# Sheet2.net
KiCad netlist of a schematic drawn in Altium Designer
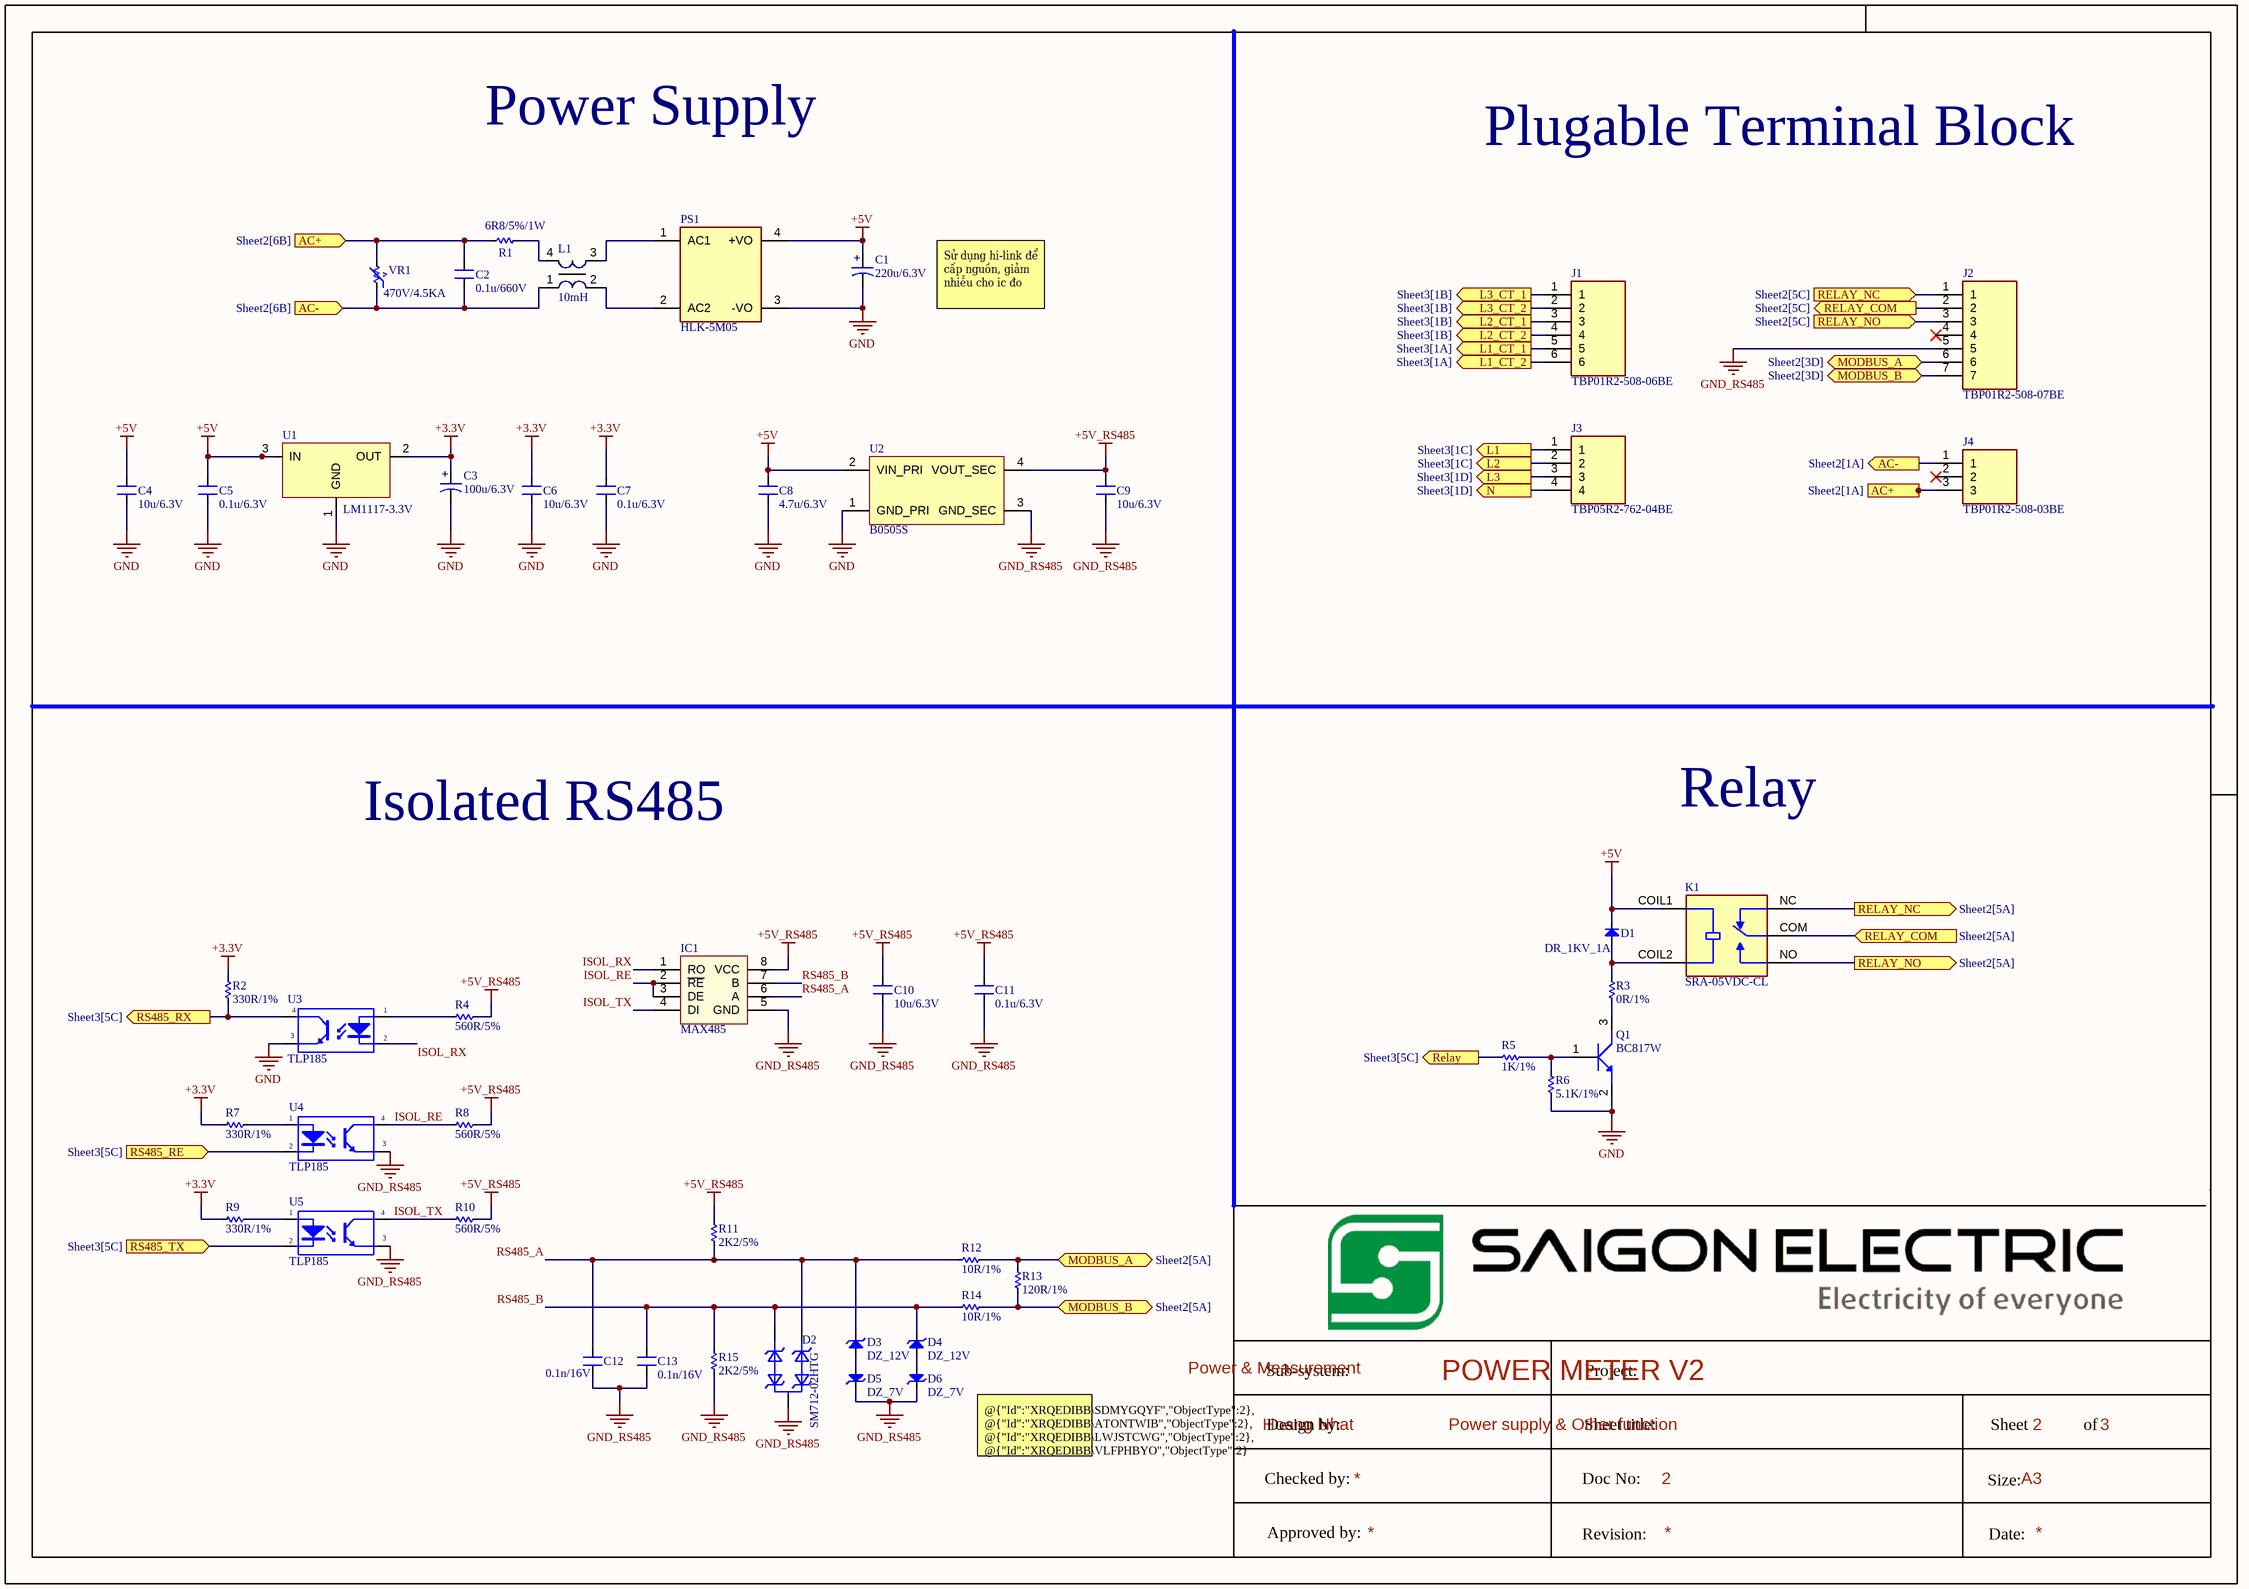
[diagram p0: Sheet2.SchDoc]

(export (version "E")
  (design (tool "Eeschema 10.0.6"))
  (components
    (comp (ref "C1")
      (value "220u/6.3V")
      (footprint "CAP-ALU-SMD-6.3x7.7x2.2")
      (libsource (lib "PowerMeter") (part "CAP_POLAR"))
    )
    (comp (ref "C2")
      (value "0.1u/660V")
      (footprint "CAPRR1500W60L1750T900H1600")
      (libsource (lib "DAK_Altium_Integrated_Lib") (part "CAP_SMD"))
    )
    (comp (ref "C3")
      (value "100u/6.3V")
      (footprint "CAP-ALU-SMD-6.3x7.7x2.2")
      (libsource (lib "PowerMeter") (part "CAP_POLAR"))
    )
    (comp (ref "C4")
      (value "10u/6.3V")
      (footprint "CAP_C_2012X110")
      (libsource (lib "DAK_Altium_Integrated_Lib") (part "CAP_SMD"))
    )
    (comp (ref "C5")
      (value "0.1u/6.3V")
      (footprint "CAP_C_2012X110")
      (libsource (lib "DAK_Altium_Integrated_Lib") (part "CAP_SMD"))
    )
    (comp (ref "C6")
      (value "10u/6.3V")
      (footprint "CAP_C_2012X110")
      (libsource (lib "DAK_Altium_Integrated_Lib") (part "CAP_SMD"))
    )
    (comp (ref "C7")
      (value "0.1u/6.3V")
      (footprint "CAP_C_2012X110")
      (libsource (lib "DAK_Altium_Integrated_Lib") (part "CAP_SMD"))
    )
    (comp (ref "C8")
      (value "4.7u/6.3V")
      (footprint "CAP_C_2012X110")
      (libsource (lib "DAK_Altium_Integrated_Lib") (part "CAP_SMD"))
    )
    (comp (ref "C9")
      (value "10u/6.3V")
      (footprint "CAP_C_2012X110")
      (libsource (lib "DAK_Altium_Integrated_Lib") (part "CAP_SMD"))
    )
    (comp (ref "C10")
      (value "10u/6.3V")
      (footprint "CAP_C_2012X110")
      (libsource (lib "DAK_Altium_Integrated_Lib") (part "CAP_SMD"))
    )
    (comp (ref "C11")
      (value "0.1u/6.3V")
      (footprint "CAP_C_2012X110")
      (libsource (lib "DAK_Altium_Integrated_Lib") (part "CAP_SMD"))
    )
    (comp (ref "C12")
      (value "0.1n/16V")
      (footprint "CAP_C_2012X110")
      (libsource (lib "DAK_Altium_Integrated_Lib") (part "CAP_SMD"))
    )
    (comp (ref "C13")
      (value "0.1n/16V")
      (footprint "CAP_C_2012X110")
      (libsource (lib "DAK_Altium_Integrated_Lib") (part "CAP_SMD"))
    )
    (comp (ref "D1")
      (value "DR_1KV_1A")
      (footprint "DIOM5025X26N")
      (description "Default Diode")
      (fields (field (name "PUBLISHER") "Altium Limited"))
      (libsource (lib "Library") (part "Diode"))
    )
    (comp (ref "D2")
      (value "SM712-02HTG")
      (footprint "SOT95P237X112-3N")
      (fields (field (name "MF") "Littelfuse Inc."))
      (libsource (lib "PowerMeter") (part "SM712-02HTG"))
    )
    (comp (ref "D3")
      (value "DZ_12V")
      (footprint "LL-34")
      (description "Zenner")
      (libsource (lib "PowerMeter") (part "DIODE Zener"))
    )
    (comp (ref "D4")
      (value "DZ_12V")
      (footprint "LL-34")
      (description "Zenner")
      (libsource (lib "PowerMeter") (part "DIODE Zener"))
    )
    (comp (ref "D5")
      (value "DZ_7V")
      (footprint "LL-34")
      (description "Zenner")
      (libsource (lib "PowerMeter") (part "DIODE Zener"))
    )
    (comp (ref "D6")
      (value "DZ_7V")
      (footprint "LL-34")
      (description "Zenner")
      (libsource (lib "PowerMeter") (part "DIODE Zener"))
    )
    (comp (ref "IC1")
      (value "MAX485")
      (footprint "SOIC-8")
      (description "RS232 - RS485 (Same sn75176)")
      (libsource (lib "PowerMeter") (part "MAX485"))
    )
    (comp (ref "J1")
      (value "TBP01R2-508-06BE")
      (footprint "CUI_TBP01R2-508-06BE")
      (fields (field (name "MF") "Same Sky"))
      (libsource (lib "PowerMeter") (part "TBP01R2-508-06BE"))
    )
    (comp (ref "J2")
      (value "TBP01R2-508-07BE")
      (footprint "CUI_TBP01R2-508-07BE")
      (description "2~24 Poles, Pluggable, Receptacle, Vertical, 5.08 Pitch, Terminal Block Connector")
      (fields (field (name "MF") "Same Sky"))
      (libsource (lib "PowerMeter") (part "TBP01R2-508-07BE"))
    )
    (comp (ref "J3")
      (value "TBP05R2-762-04BE")
      (footprint "CUI_TBP05R2-762-04BE")
      (description "2~24 Poles, Pluggable, Receptacle, Vertical, 7.62 Pitch, Terminal Block Connector")
      (fields (field (name "MF") "Same Sky"))
      (libsource (lib "PowerMeter") (part "TBP05R2-762-04BE"))
    )
    (comp (ref "J4")
      (value "TBP01R2-508-03BE")
      (footprint "CUI_TBP01R2-508-03BE")
      (description "2~24 Poles, Pluggable, Receptacle, Vertical, 5.08 Pitch, Terminal Block Connector")
      (fields (field (name "MF") "Same Sky"))
      (libsource (lib "PowerMeter") (part "TBP01R2-508-03BE"))
    )
    (comp (ref "K1")
      (value "SRA-05VDC-CL")
      (footprint "RELAY_SRA-05VDC-CL")
      (fields (field (name "MF") "Songle Relay"))
      (libsource (lib "PowerMeter") (part "SRA-05VDC-CL"))
    )
    (comp (ref "L1")
      (value "10mH")
      (footprint "UU98LFH142LF")
      (fields
        (field (name "PARTNO") "744284100")
        (field (name "MANUFACTURER") "Würth Elektronik eiSos GmbH")
        (field (name "CREATED BY") "Christin Zierenner")
      )
      (libsource (lib "Library") (part "L-DIP-2"))
    )
    (comp (ref "PS1")
      (value "HLK-5M05")
      (footprint "CONV_HLK-5M05")
      (description "AC DC 220V to 5V 5W 5Watt Isolated Switching Step-Down Power Supply Module Converter")
      (fields (field (name "MF") "Hi-link"))
      (libsource (lib "PowerMeter") (part "HLK-5M05"))
    )
    (comp (ref "Q1") (value "BC817W") (footprint "SOT-323") (libsource (lib "PowerMeter") (part "BJT_NPN")))
    (comp (ref "R1")
      (value "6R8/5%/1W")
      (footprint "RES-1W")
      (description "Resistor")
      (fields
        (field (name "MANUFACTURER") "Generic Components")
        (field (name "PUBLISHER") "Altium Hobart Technology Centre")
      )
      (libsource (lib "Library") (part "Res-SMD"))
    )
    (comp (ref "R2")
      (value "330R/1%")
      (footprint "RES_C_2012X65")
      (description "Resistor")
      (fields
        (field (name "MANUFACTURER") "Generic Components")
        (field (name "PUBLISHER") "Altium Hobart Technology Centre")
      )
      (libsource (lib "Library") (part "Res-SMD"))
    )
    (comp (ref "R3")
      (value "0R/1%")
      (footprint "RES_C_2012X65")
      (description "Resistor")
      (fields
        (field (name "MANUFACTURER") "Generic Components")
        (field (name "PUBLISHER") "Altium Hobart Technology Centre")
      )
      (libsource (lib "Library") (part "Res-SMD"))
    )
    (comp (ref "R4")
      (value "560R/5%")
      (footprint "RES_C_2012X65")
      (description "Resistor")
      (fields
        (field (name "MANUFACTURER") "Generic Components")
        (field (name "PUBLISHER") "Altium Hobart Technology Centre")
      )
      (libsource (lib "Library") (part "Res-SMD"))
    )
    (comp (ref "R5")
      (value "1K/1%")
      (footprint "RES_C_2012X65")
      (description "Resistor")
      (fields
        (field (name "MANUFACTURER") "Generic Components")
        (field (name "PUBLISHER") "Altium Hobart Technology Centre")
      )
      (libsource (lib "Library") (part "Res-SMD"))
    )
    (comp (ref "R6")
      (value "5.1K/1%")
      (footprint "RES_C_2012X65")
      (description "Resistor")
      (fields
        (field (name "MANUFACTURER") "Generic Components")
        (field (name "PUBLISHER") "Altium Hobart Technology Centre")
      )
      (libsource (lib "Library") (part "Res-SMD"))
    )
    (comp (ref "R7")
      (value "330R/1%")
      (footprint "RES_C_2012X65")
      (description "Resistor")
      (fields
        (field (name "MANUFACTURER") "Generic Components")
        (field (name "PUBLISHER") "Altium Hobart Technology Centre")
      )
      (libsource (lib "Library") (part "Res-SMD"))
    )
    (comp (ref "R8")
      (value "560R/5%")
      (footprint "RES_C_2012X65")
      (description "Resistor")
      (fields
        (field (name "MANUFACTURER") "Generic Components")
        (field (name "PUBLISHER") "Altium Hobart Technology Centre")
      )
      (libsource (lib "Library") (part "Res-SMD"))
    )
    (comp (ref "R9")
      (value "330R/1%")
      (footprint "RES_C_2012X65")
      (description "Resistor")
      (fields
        (field (name "MANUFACTURER") "Generic Components")
        (field (name "PUBLISHER") "Altium Hobart Technology Centre")
      )
      (libsource (lib "Library") (part "Res-SMD"))
    )
    (comp (ref "R10")
      (value "560R/5%")
      (footprint "RES_C_2012X65")
      (description "Resistor")
      (fields
        (field (name "MANUFACTURER") "Generic Components")
        (field (name "PUBLISHER") "Altium Hobart Technology Centre")
      )
      (libsource (lib "Library") (part "Res-SMD"))
    )
    (comp (ref "R11")
      (value "2K2/5%")
      (footprint "RES_C_2012X65")
      (description "Resistor")
      (fields
        (field (name "MANUFACTURER") "Generic Components")
        (field (name "PUBLISHER") "Altium Hobart Technology Centre")
      )
      (libsource (lib "Library") (part "Res-SMD"))
    )
    (comp (ref "R12")
      (value "10R/1%")
      (footprint "RES_C_3216X70")
      (description "Resistor")
      (fields
        (field (name "MANUFACTURER") "Generic Components")
        (field (name "PUBLISHER") "Altium Hobart Technology Centre")
      )
      (libsource (lib "Library") (part "Res-SMD"))
    )
    (comp (ref "R13")
      (value "120R/1%")
      (footprint "RES_C_3216X70")
      (description "Resistor")
      (fields
        (field (name "MANUFACTURER") "Generic Components")
        (field (name "PUBLISHER") "Altium Hobart Technology Centre")
      )
      (libsource (lib "Library") (part "Res-SMD"))
    )
    (comp (ref "R14")
      (value "10R/1%")
      (footprint "RES_C_3216X70")
      (description "Resistor")
      (fields
        (field (name "MANUFACTURER") "Generic Components")
        (field (name "PUBLISHER") "Altium Hobart Technology Centre")
      )
      (libsource (lib "Library") (part "Res-SMD"))
    )
    (comp (ref "R15")
      (value "2K2/5%")
      (footprint "RES_C_2012X65")
      (description "Resistor")
      (fields
        (field (name "MANUFACTURER") "Generic Components")
        (field (name "PUBLISHER") "Altium Hobart Technology Centre")
      )
      (libsource (lib "Library") (part "Res-SMD"))
    )
    (comp (ref "U1")
      (value "LM1117-3.3V")
      (footprint "SOT230P700X180-4N")
      (description "800mA Low-Dropout Linear Regulator")
      (fields (field (name "CREATOR") "Nguyen Ba Bien"))
      (libsource (lib "PowerMeter") (part "LM1117"))
    )
    (comp (ref "U2") (value "B0505S") (footprint "B0505S-1W") (libsource (lib "PowerMeter") (part "B0505S")))
    (comp (ref "U3")
      (value "TLP185")
      (footprint "SOP254P700X220-4N")
      (description "Single Opto")
      (libsource (lib "PowerMeter") (part "TLP185"))
    )
    (comp (ref "U4")
      (value "TLP185")
      (footprint "SOP254P700X220-4N")
      (description "Single Opto")
      (libsource (lib "PowerMeter") (part "TLP185"))
    )
    (comp (ref "U5")
      (value "TLP185")
      (footprint "SOP254P700X220-4N")
      (description "Single Opto")
      (libsource (lib "PowerMeter") (part "TLP185"))
    )
    (comp (ref "VR1")
      (value "470V/4.5KA")
      (footprint "B72214P2301K101")
      (description "MOV-14D471K, Varistors 470V 14mm")
      (libsource (lib "PowerMeter") (part "Varistor"))
    )
  )
  (nets
    (net (code "1") (name "+3.3V") (class "Default")
      (node (ref "C3") (pin "1") (pinfunction "1_1") (pintype "passive"))
      (node (ref "C6") (pin "2") (pinfunction "2_2") (pintype "passive"))
      (node (ref "C7") (pin "2") (pinfunction "2_2") (pintype "passive"))
      (node (ref "R2") (pin "1") (pinfunction "1_1") (pintype "passive"))
      (node (ref "R7") (pin "1") (pinfunction "1_1") (pintype "passive"))
      (node (ref "R9") (pin "1") (pinfunction "1_1") (pintype "passive"))
      (node (ref "U1") (pin "2") (pinfunction "OUT_2") (pintype "passive"))
    )
    (net (code "2") (name "+5V") (class "Default")
      (node (ref "C1") (pin "1") (pinfunction "1_1") (pintype "passive"))
      (node (ref "C4") (pin "2") (pinfunction "2_2") (pintype "passive"))
      (node (ref "C5") (pin "2") (pinfunction "2_2") (pintype "passive"))
      (node (ref "C8") (pin "2") (pinfunction "2_2") (pintype "passive"))
      (node (ref "D1") (pin "2") (pinfunction "K_2") (pintype "passive"))
      (node (ref "K1") (pin "COIL1") (pinfunction "COIL1_COIL1") (pintype "passive"))
      (node (ref "PS1") (pin "4") (pinfunction "+VO_4") (pintype "passive"))
      (node (ref "U1") (pin "3") (pinfunction "IN_3") (pintype "passive"))
      (node (ref "U2") (pin "2") (pinfunction "VIN_PRI_2") (pintype "passive"))
    )
    (net (code "3") (name "+5V_RS485") (class "Default")
      (node (ref "C10") (pin "2") (pinfunction "2_2") (pintype "passive"))
      (node (ref "C11") (pin "2") (pinfunction "2_2") (pintype "passive"))
      (node (ref "C9") (pin "2") (pinfunction "2_2") (pintype "passive"))
      (node (ref "IC1") (pin "8") (pinfunction "VCC_8") (pintype "passive"))
      (node (ref "R10") (pin "2") (pinfunction "2_2") (pintype "passive"))
      (node (ref "R11") (pin "2") (pinfunction "2_2") (pintype "passive"))
      (node (ref "R4") (pin "2") (pinfunction "2_2") (pintype "passive"))
      (node (ref "R8") (pin "2") (pinfunction "2_2") (pintype "passive"))
      (node (ref "U2") (pin "4") (pinfunction "VOUT_SEC_4") (pintype "passive"))
    )
    (net (code "4") (name "/AC+") (class "Default")
      (node (ref "C2") (pin "2") (pinfunction "2_2") (pintype "passive"))
      (node (ref "J4") (pin "3") (pinfunction "3_3") (pintype "passive"))
      (node (ref "R1") (pin "1") (pinfunction "1_1") (pintype "passive"))
      (node (ref "VR1") (pin "1") (pinfunction "1_1") (pintype "passive"))
    )
    (net (code "5") (name "/AC-") (class "Default")
      (node (ref "C2") (pin "1") (pinfunction "1_1") (pintype "passive"))
      (node (ref "J4") (pin "1") (pinfunction "1_1") (pintype "passive"))
      (node (ref "L1") (pin "1") (pinfunction "1_1") (pintype "passive"))
      (node (ref "VR1") (pin "2") (pinfunction "2_2") (pintype "passive"))
    )
    (net (code "6") (name "/ISOL_RE") (class "Default")
      (node (ref "IC1") (pin "2") (pinfunction "~{RE}_2") (pintype "passive"))
      (node (ref "IC1") (pin "3") (pinfunction "DE_3") (pintype "passive"))
      (node (ref "R8") (pin "1") (pinfunction "1_1") (pintype "passive"))
      (node (ref "U4") (pin "4") (pinfunction "C_4") (pintype "passive"))
    )
    (net (code "7") (name "/ISOL_RX") (class "Default")
      (node (ref "IC1") (pin "1") (pinfunction "RO_1") (pintype "passive"))
      (node (ref "U3") (pin "2") (pinfunction "K_2") (pintype "passive"))
    )
    (net (code "8") (name "/ISOL_TX") (class "Default")
      (node (ref "IC1") (pin "4") (pinfunction "DI_4") (pintype "passive"))
      (node (ref "R10") (pin "1") (pinfunction "1_1") (pintype "passive"))
      (node (ref "U5") (pin "4") (pinfunction "C_4") (pintype "passive"))
    )
    (net (code "9") (name "/L1") (class "Default")
      (node (ref "J3") (pin "1") (pinfunction "1_1") (pintype "passive"))
    )
    (net (code "10") (name "/L1_CT_1") (class "Default")
      (node (ref "J1") (pin "5") (pinfunction "5_5") (pintype "passive"))
    )
    (net (code "11") (name "/L1_CT_2") (class "Default")
      (node (ref "J1") (pin "6") (pinfunction "6_6") (pintype "passive"))
    )
    (net (code "12") (name "/L2") (class "Default")
      (node (ref "J3") (pin "2") (pinfunction "2_2") (pintype "passive"))
    )
    (net (code "13") (name "/L2_CT_1") (class "Default")
      (node (ref "J1") (pin "3") (pinfunction "3_3") (pintype "passive"))
    )
    (net (code "14") (name "/L2_CT_2") (class "Default")
      (node (ref "J1") (pin "4") (pinfunction "4_4") (pintype "passive"))
    )
    (net (code "15") (name "/L3") (class "Default")
      (node (ref "J3") (pin "3") (pinfunction "3_3") (pintype "passive"))
    )
    (net (code "16") (name "/L3_CT_1") (class "Default")
      (node (ref "J1") (pin "1") (pinfunction "1_1") (pintype "passive"))
    )
    (net (code "17") (name "/L3_CT_2") (class "Default")
      (node (ref "J1") (pin "2") (pinfunction "2_2") (pintype "passive"))
    )
    (net (code "18") (name "/MODBUS_A") (class "Default")
      (node (ref "J2") (pin "6") (pinfunction "6_6") (pintype "passive"))
      (node (ref "R12") (pin "2") (pinfunction "2_2") (pintype "passive"))
      (node (ref "R13") (pin "2") (pinfunction "2_2") (pintype "passive"))
    )
    (net (code "19") (name "/MODBUS_B") (class "Default")
      (node (ref "J2") (pin "7") (pinfunction "7_7") (pintype "passive"))
      (node (ref "R13") (pin "1") (pinfunction "1_1") (pintype "passive"))
      (node (ref "R14") (pin "2") (pinfunction "2_2") (pintype "passive"))
    )
    (net (code "20") (name "/N") (class "Default")
      (node (ref "J3") (pin "4") (pinfunction "4_4") (pintype "passive"))
    )
    (net (code "21") (name "/RELAY_COM") (class "Default")
      (node (ref "J2") (pin "2") (pinfunction "2_2") (pintype "passive"))
      (node (ref "K1") (pin "COM") (pinfunction "COM_COM") (pintype "passive"))
    )
    (net (code "22") (name "/RELAY_NC") (class "Default")
      (node (ref "J2") (pin "1") (pinfunction "1_1") (pintype "passive"))
      (node (ref "K1") (pin "NC") (pinfunction "NC_NC") (pintype "passive"))
    )
    (net (code "23") (name "/RELAY_NO") (class "Default")
      (node (ref "J2") (pin "3") (pinfunction "3_3") (pintype "passive"))
      (node (ref "K1") (pin "NO") (pinfunction "NO_NO") (pintype "passive"))
    )
    (net (code "24") (name "/RS485_A") (class "Default")
      (node (ref "C12") (pin "2") (pinfunction "2_2") (pintype "passive"))
      (node (ref "D2") (pin "1") (pinfunction "1_1") (pintype "passive"))
      (node (ref "D3") (pin "1") (pinfunction "K_1") (pintype "passive"))
      (node (ref "IC1") (pin "6") (pinfunction "A_6") (pintype "passive"))
      (node (ref "R11") (pin "1") (pinfunction "1_1") (pintype "passive"))
      (node (ref "R12") (pin "1") (pinfunction "1_1") (pintype "passive"))
    )
    (net (code "25") (name "/RS485_B") (class "Default")
      (node (ref "C13") (pin "2") (pinfunction "2_2") (pintype "passive"))
      (node (ref "D2") (pin "2") (pinfunction "2_2") (pintype "passive"))
      (node (ref "D4") (pin "1") (pinfunction "K_1") (pintype "passive"))
      (node (ref "IC1") (pin "7") (pinfunction "B_7") (pintype "passive"))
      (node (ref "R14") (pin "1") (pinfunction "1_1") (pintype "passive"))
      (node (ref "R15") (pin "2") (pinfunction "2_2") (pintype "passive"))
    )
    (net (code "26") (name "/RS485_RE") (class "Default")
      (node (ref "U4") (pin "2") (pinfunction "K_2") (pintype "passive"))
    )
    (net (code "27") (name "/RS485_RX") (class "Default")
      (node (ref "R2") (pin "2") (pinfunction "2_2") (pintype "passive"))
      (node (ref "U3") (pin "4") (pinfunction "C_4") (pintype "passive"))
    )
    (net (code "28") (name "/RS485_TX") (class "Default")
      (node (ref "U5") (pin "2") (pinfunction "K_2") (pintype "passive"))
    )
    (net (code "29") (name "/Relay") (class "Default")
      (node (ref "R5") (pin "1") (pinfunction "1_1") (pintype "passive"))
    )
    (net (code "30") (name "GND") (class "Default")
      (node (ref "C1") (pin "2") (pinfunction "2_2") (pintype "passive"))
      (node (ref "C3") (pin "2") (pinfunction "2_2") (pintype "passive"))
      (node (ref "C4") (pin "1") (pinfunction "1_1") (pintype "passive"))
      (node (ref "C5") (pin "1") (pinfunction "1_1") (pintype "passive"))
      (node (ref "C6") (pin "1") (pinfunction "1_1") (pintype "passive"))
      (node (ref "C7") (pin "1") (pinfunction "1_1") (pintype "passive"))
      (node (ref "C8") (pin "1") (pinfunction "1_1") (pintype "passive"))
      (node (ref "PS1") (pin "3") (pinfunction "-VO_3") (pintype "passive"))
      (node (ref "Q1") (pin "2") (pinfunction "E_2") (pintype "passive"))
      (node (ref "R6") (pin "1") (pinfunction "1_1") (pintype "passive"))
      (node (ref "U1") (pin "1") (pinfunction "GND_1") (pintype "passive"))
      (node (ref "U2") (pin "1") (pinfunction "GND_PRI_1") (pintype "passive"))
      (node (ref "U3") (pin "3") (pinfunction "E_3") (pintype "passive"))
    )
    (net (code "31") (name "GND_RS485") (class "Default")
      (node (ref "C10") (pin "1") (pinfunction "1_1") (pintype "passive"))
      (node (ref "C11") (pin "1") (pinfunction "1_1") (pintype "passive"))
      (node (ref "C12") (pin "1") (pinfunction "1_1") (pintype "passive"))
      (node (ref "C13") (pin "1") (pinfunction "1_1") (pintype "passive"))
      (node (ref "C9") (pin "1") (pinfunction "1_1") (pintype "passive"))
      (node (ref "D2") (pin "3") (pinfunction "3_3") (pintype "passive"))
      (node (ref "D5") (pin "1") (pinfunction "K_1") (pintype "passive"))
      (node (ref "D6") (pin "1") (pinfunction "K_1") (pintype "passive"))
      (node (ref "IC1") (pin "5") (pinfunction "GND_5") (pintype "passive"))
      (node (ref "J2") (pin "5") (pinfunction "5_5") (pintype "passive"))
      (node (ref "R15") (pin "1") (pinfunction "1_1") (pintype "passive"))
      (node (ref "U2") (pin "3") (pinfunction "GND_SEC_3") (pintype "passive"))
      (node (ref "U4") (pin "3") (pinfunction "E_3") (pintype "passive"))
      (node (ref "U5") (pin "3") (pinfunction "E_3") (pintype "passive"))
    )
    (net (code "32") (name "Net-(D1-A)") (class "Default")
      (node (ref "D1") (pin "1") (pinfunction "A_1") (pintype "passive"))
      (node (ref "K1") (pin "COIL2") (pinfunction "COIL2_COIL2") (pintype "passive"))
      (node (ref "R3") (pin "2") (pinfunction "2_2") (pintype "passive"))
    )
    (net (code "33") (name "Net-(D3-A)") (class "Default")
      (node (ref "D3") (pin "2") (pinfunction "A_2") (pintype "passive"))
      (node (ref "D5") (pin "2") (pinfunction "A_2") (pintype "passive"))
    )
    (net (code "34") (name "Net-(D4-A)") (class "Default")
      (node (ref "D4") (pin "2") (pinfunction "A_2") (pintype "passive"))
      (node (ref "D6") (pin "2") (pinfunction "A_2") (pintype "passive"))
    )
    (net (code "35") (name "Net-(L1-Pad4)") (class "Default")
      (node (ref "L1") (pin "4") (pinfunction "4_4") (pintype "passive"))
      (node (ref "R1") (pin "2") (pinfunction "2_2") (pintype "passive"))
    )
    (net (code "36") (name "Net-(PS1-AC1)") (class "Default")
      (node (ref "L1") (pin "3") (pinfunction "3_3") (pintype "passive"))
      (node (ref "PS1") (pin "1") (pinfunction "AC1_1") (pintype "passive"))
    )
    (net (code "37") (name "Net-(PS1-AC2)") (class "Default")
      (node (ref "L1") (pin "2") (pinfunction "2_2") (pintype "passive"))
      (node (ref "PS1") (pin "2") (pinfunction "AC2_2") (pintype "passive"))
    )
    (net (code "38") (name "Net-(Q1-B)") (class "Default")
      (node (ref "Q1") (pin "1") (pinfunction "B_1") (pintype "passive"))
      (node (ref "R5") (pin "2") (pinfunction "2_2") (pintype "passive"))
      (node (ref "R6") (pin "2") (pinfunction "2_2") (pintype "passive"))
    )
    (net (code "39") (name "Net-(Q1-C)") (class "Default")
      (node (ref "Q1") (pin "3") (pinfunction "C_3") (pintype "passive"))
      (node (ref "R3") (pin "1") (pinfunction "1_1") (pintype "passive"))
    )
    (net (code "40") (name "Net-(U3-A)") (class "Default")
      (node (ref "R4") (pin "1") (pinfunction "1_1") (pintype "passive"))
      (node (ref "U3") (pin "1") (pinfunction "A_1") (pintype "passive"))
    )
    (net (code "41") (name "Net-(U4-A)") (class "Default")
      (node (ref "R7") (pin "2") (pinfunction "2_2") (pintype "passive"))
      (node (ref "U4") (pin "1") (pinfunction "A_1") (pintype "passive"))
    )
    (net (code "42") (name "Net-(U5-A)") (class "Default")
      (node (ref "R9") (pin "2") (pinfunction "2_2") (pintype "passive"))
      (node (ref "U5") (pin "1") (pinfunction "A_1") (pintype "passive"))
    )
    (net (code "43") (name "unconnected-(J2-Pad4)") (class "Default")
      (node (ref "J2") (pin "4") (pinfunction "4_4") (pintype "passive+no_connect"))
    )
    (net (code "44") (name "unconnected-(J4-Pad2)") (class "Default")
      (node (ref "J4") (pin "2") (pinfunction "2_2") (pintype "passive+no_connect"))
    )
  )
)
